# pj14.net
KiCad netlist of a schematic drawn in EAGLE
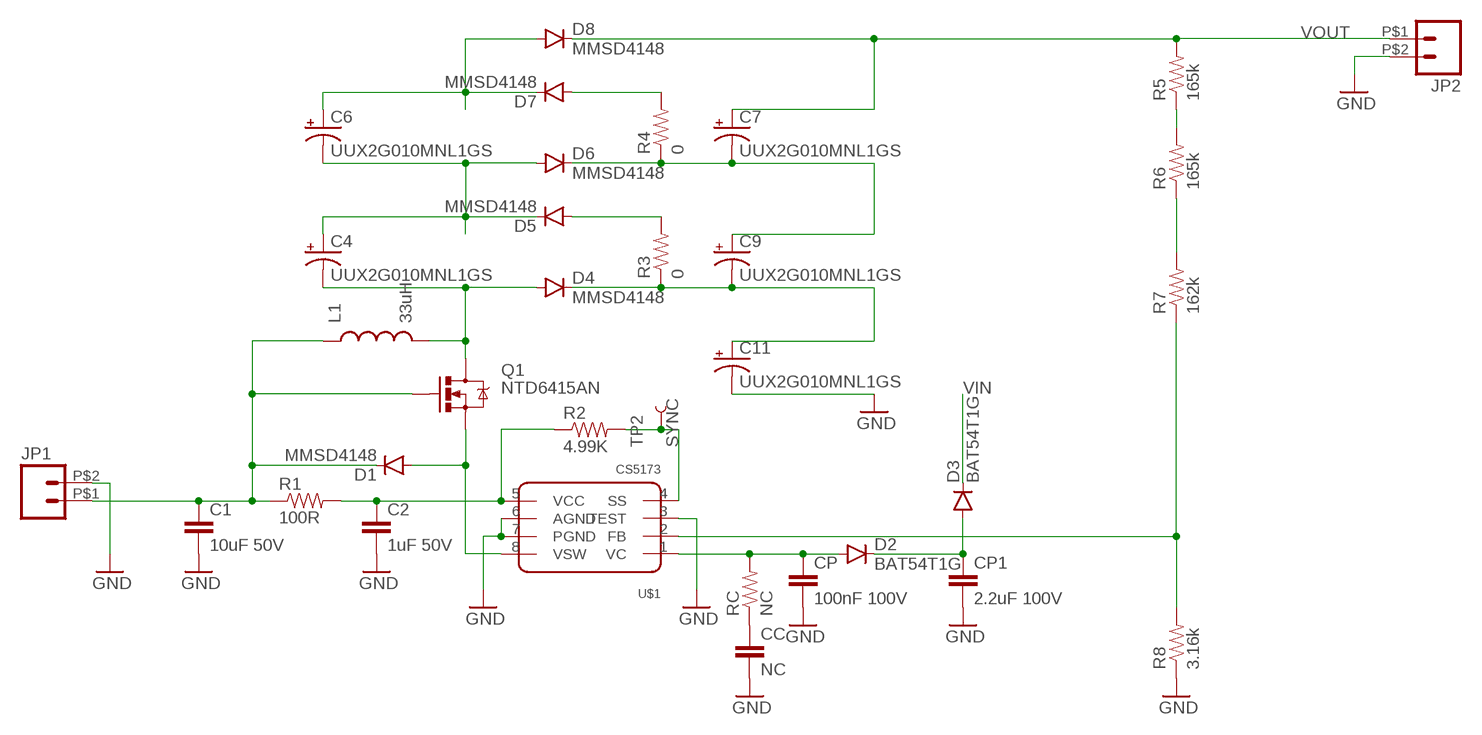
[diagram p0: schematic, sheet 1]

(export (version "E")
  (design (tool "Eeschema 10.0.6"))
  (components
    (comp (ref "C1")
      (value "10uF 50V")
      (footprint "eagle-import:1210")
      (libsource (lib "eagle-import") (part "10UF50V20%(1210)"))
    )
    (comp (ref "C2")
      (value "1uF 50V")
      (footprint "eagle-import:1210")
      (libsource (lib "eagle-import") (part "10UF50V20%(1210)"))
    )
    (comp (ref "C4")
      (value "UUX2G010MNL1GS")
      (footprint "eagle-import:PANASONIC_E")
      (libsource (lib "eagle-import") (part "CAP_POLE"))
    )
    (comp (ref "C6")
      (value "UUX2G010MNL1GS")
      (footprint "eagle-import:PANASONIC_E")
      (libsource (lib "eagle-import") (part "CAP_POLE"))
    )
    (comp (ref "C7")
      (value "UUX2G010MNL1GS")
      (footprint "eagle-import:PANASONIC_E")
      (libsource (lib "eagle-import") (part "CAP_POLE"))
    )
    (comp (ref "C9")
      (value "UUX2G010MNL1GS")
      (footprint "eagle-import:PANASONIC_E")
      (libsource (lib "eagle-import") (part "CAP_POLE"))
    )
    (comp (ref "C11")
      (value "UUX2G010MNL1GS")
      (footprint "eagle-import:PANASONIC_E")
      (libsource (lib "eagle-import") (part "CAP_POLE"))
    )
    (comp (ref "CC")
      (value "NC")
      (footprint "eagle-import:0603-CAP")
      (libsource (lib "eagle-import") (part "1.2PF-50V-20%(0603)"))
    )
    (comp (ref "CP")
      (value "100nF 100V")
      (footprint "eagle-import:0603-CAP")
      (libsource (lib "eagle-import") (part "1.2PF-50V-20%(0603)"))
    )
    (comp (ref "CP1")
      (value "2.2uF 100V")
      (footprint "eagle-import:1210")
      (libsource (lib "eagle-import") (part "10UF50V20%(1210)"))
    )
    (comp (ref "D1")
      (value "MMSD4148")
      (footprint "eagle-import:SOD-123")
      (libsource (lib "eagle-import") (part "DIODESOD123"))
    )
    (comp (ref "D2")
      (value "BAT54T1G")
      (footprint "eagle-import:SOD-123")
      (libsource (lib "eagle-import") (part "DIODESOD123"))
    )
    (comp (ref "D3")
      (value "BAT54T1G")
      (footprint "eagle-import:SOD-123")
      (libsource (lib "eagle-import") (part "DIODESOD123"))
    )
    (comp (ref "D4")
      (value "MMSD4148")
      (footprint "eagle-import:SOD-123")
      (libsource (lib "eagle-import") (part "DIODESOD123"))
    )
    (comp (ref "D5")
      (value "MMSD4148")
      (footprint "eagle-import:SOD-123")
      (libsource (lib "eagle-import") (part "DIODESOD123"))
    )
    (comp (ref "D6")
      (value "MMSD4148")
      (footprint "eagle-import:SOD-123")
      (libsource (lib "eagle-import") (part "DIODESOD123"))
    )
    (comp (ref "D7")
      (value "MMSD4148")
      (footprint "eagle-import:SOD-123")
      (libsource (lib "eagle-import") (part "DIODESOD123"))
    )
    (comp (ref "D8")
      (value "MMSD4148")
      (footprint "eagle-import:SOD-123")
      (libsource (lib "eagle-import") (part "DIODESOD123"))
    )
    (comp (ref "JP1")
      (value "M02")
      (footprint "eagle-import:1X02_5.08")
      (libsource (lib "eagle-import") (part "M02"))
    )
    (comp (ref "JP2")
      (value "M02")
      (footprint "eagle-import:1X02_5.08")
      (libsource (lib "eagle-import") (part "M02"))
    )
    (comp (ref "L1")
      (value "33uH")
      (footprint "eagle-import:CDRH125")
      (libsource (lib "eagle-import") (part "INDUCTORPWR"))
    )
    (comp (ref "Q1")
      (value "NTD6415AN")
      (footprint "eagle-import:DPAK")
      (libsource (lib "eagle-import") (part "MOSFET-NCHANNELFDD8780"))
    )
    (comp (ref "R1")
      (value "100R")
      (footprint "eagle-import:0603-RES")
      (libsource (lib "eagle-import") (part "2.0KOHM1/10W5%(0603)"))
    )
    (comp (ref "R2")
      (value "4.99K")
      (footprint "eagle-import:0603-RES")
      (libsource (lib "eagle-import") (part "2.0KOHM1/10W5%(0603)"))
    )
    (comp (ref "R3")
      (value "0")
      (footprint "eagle-import:0603-RES")
      (libsource (lib "eagle-import") (part "2.0KOHM1/10W5%(0603)"))
    )
    (comp (ref "R4")
      (value "0")
      (footprint "eagle-import:0603-RES")
      (libsource (lib "eagle-import") (part "2.0KOHM1/10W5%(0603)"))
    )
    (comp (ref "R5")
      (value "165k")
      (footprint "eagle-import:0603-RES")
      (libsource (lib "eagle-import") (part "2.0KOHM1/10W5%(0603)"))
    )
    (comp (ref "R6")
      (value "165k")
      (footprint "eagle-import:0603-RES")
      (libsource (lib "eagle-import") (part "2.0KOHM1/10W5%(0603)"))
    )
    (comp (ref "R7")
      (value "162k")
      (footprint "eagle-import:0603-RES")
      (libsource (lib "eagle-import") (part "2.0KOHM1/10W5%(0603)"))
    )
    (comp (ref "R8")
      (value "3.16k")
      (footprint "eagle-import:0603-RES")
      (libsource (lib "eagle-import") (part "2.0KOHM1/10W5%(0603)"))
    )
    (comp (ref "RC")
      (value "NC")
      (footprint "eagle-import:0603-RES")
      (libsource (lib "eagle-import") (part "2.0KOHM1/10W5%(0603)"))
    )
    (comp (ref "TP2")
      (value "SYNC")
      (footprint "eagle-import:PAD.03X.03")
      (libsource (lib "eagle-import") (part "TEST-POINT3"))
    )
    (comp (ref "U$1")
      (value "CS5173")
      (footprint "eagle-import:SOIC−8")
      (libsource (lib "eagle-import") (part "CS5173"))
    )
  )
  (nets
    (net (code "1") (name "/VIN") (class "Default")
      (node (ref "C1") (pin "1") (pinfunction "1_1") (pintype "passive"))
      (node (ref "D1") (pin "C") (pinfunction "C_C") (pintype "passive"))
      (node (ref "D3") (pin "C") (pinfunction "C_C") (pintype "passive"))
      (node (ref "JP1") (pin "P$1") (pinfunction "1_P$1") (pintype "passive"))
      (node (ref "L1") (pin "1") (pinfunction "1_1") (pintype "passive"))
      (node (ref "Q1") (pin "1") (pinfunction "G_1") (pintype "passive"))
      (node (ref "R1") (pin "1") (pinfunction "1_1") (pintype "passive"))
    )
    (net (code "2") (name "/VOUT") (class "Default")
      (node (ref "C7") (pin "+") (pinfunction "+_+") (pintype "passive"))
      (node (ref "D8") (pin "C") (pinfunction "C_C") (pintype "passive"))
      (node (ref "JP2") (pin "P$1") (pinfunction "1_P$1") (pintype "passive"))
      (node (ref "R5") (pin "2") (pinfunction "2_2") (pintype "passive"))
    )
    (net (code "3") (name "GND") (class "Default")
      (node (ref "C1") (pin "2") (pinfunction "2_2") (pintype "passive"))
      (node (ref "C11") (pin "-") (pinfunction "-_-") (pintype "passive"))
      (node (ref "C2") (pin "2") (pinfunction "2_2") (pintype "passive"))
      (node (ref "CC") (pin "2") (pinfunction "2_2") (pintype "passive"))
      (node (ref "CP") (pin "2") (pinfunction "2_2") (pintype "passive"))
      (node (ref "CP1") (pin "2") (pinfunction "2_2") (pintype "passive"))
      (node (ref "JP1") (pin "P$2") (pinfunction "2_P$2") (pintype "passive"))
      (node (ref "JP2") (pin "P$2") (pinfunction "2_P$2") (pintype "passive"))
      (node (ref "R8") (pin "1") (pinfunction "1_1") (pintype "passive"))
      (node (ref "U$1") (pin "3") (pinfunction "TEST_3") (pintype "bidirectional"))
      (node (ref "U$1") (pin "6") (pinfunction "AGND_6") (pintype "bidirectional"))
      (node (ref "U$1") (pin "7") (pinfunction "PGND_7") (pintype "bidirectional"))
    )
    (net (code "4") (name "Net-(C4-Pad+)") (class "Default")
      (node (ref "C4") (pin "+") (pinfunction "+_+") (pintype "passive"))
      (node (ref "C6") (pin "-") (pinfunction "-_-") (pintype "passive"))
      (node (ref "D5") (pin "C") (pinfunction "C_C") (pintype "passive"))
      (node (ref "D6") (pin "A") (pinfunction "A_A") (pintype "passive"))
    )
    (net (code "5") (name "Net-(C6-Pad+)") (class "Default")
      (node (ref "C6") (pin "+") (pinfunction "+_+") (pintype "passive"))
      (node (ref "D7") (pin "C") (pinfunction "C_C") (pintype "passive"))
      (node (ref "D8") (pin "A") (pinfunction "A_A") (pintype "passive"))
    )
    (net (code "6") (name "Net-(C7-Pad-)") (class "Default")
      (node (ref "C7") (pin "-") (pinfunction "-_-") (pintype "passive"))
      (node (ref "C9") (pin "+") (pinfunction "+_+") (pintype "passive"))
      (node (ref "D6") (pin "C") (pinfunction "C_C") (pintype "passive"))
      (node (ref "R4") (pin "1") (pinfunction "1_1") (pintype "passive"))
    )
    (net (code "7") (name "Net-(C11-Pad+)") (class "Default")
      (node (ref "C11") (pin "+") (pinfunction "+_+") (pintype "passive"))
      (node (ref "C9") (pin "-") (pinfunction "-_-") (pintype "passive"))
      (node (ref "D4") (pin "C") (pinfunction "C_C") (pintype "passive"))
      (node (ref "R3") (pin "1") (pinfunction "1_1") (pintype "passive"))
    )
    (net (code "8") (name "Net-(CC-Pad1)") (class "Default")
      (node (ref "CC") (pin "1") (pinfunction "1_1") (pintype "passive"))
      (node (ref "RC") (pin "1") (pinfunction "1_1") (pintype "passive"))
    )
    (net (code "9") (name "Net-(CP1-Pad1)") (class "Default")
      (node (ref "CP1") (pin "1") (pinfunction "1_1") (pintype "passive"))
      (node (ref "D2") (pin "C") (pinfunction "C_C") (pintype "passive"))
      (node (ref "D3") (pin "A") (pinfunction "A_A") (pintype "passive"))
    )
    (net (code "10") (name "Net-(D5-PadA)") (class "Default")
      (node (ref "D5") (pin "A") (pinfunction "A_A") (pintype "passive"))
      (node (ref "R3") (pin "2") (pinfunction "2_2") (pintype "passive"))
    )
    (net (code "11") (name "Net-(D7-PadA)") (class "Default")
      (node (ref "D7") (pin "A") (pinfunction "A_A") (pintype "passive"))
      (node (ref "R4") (pin "2") (pinfunction "2_2") (pintype "passive"))
    )
    (net (code "12") (name "Net-(Q1-D)") (class "Default")
      (node (ref "C4") (pin "-") (pinfunction "-_-") (pintype "passive"))
      (node (ref "D4") (pin "A") (pinfunction "A_A") (pintype "passive"))
      (node (ref "L1") (pin "2") (pinfunction "2_2") (pintype "passive"))
      (node (ref "Q1") (pin "4") (pinfunction "D_4") (pintype "passive"))
    )
    (net (code "13") (name "Net-(Q1-S)") (class "Default")
      (node (ref "D1") (pin "A") (pinfunction "A_A") (pintype "passive"))
      (node (ref "Q1") (pin "3") (pinfunction "S_3") (pintype "passive"))
      (node (ref "U$1") (pin "8") (pinfunction "VSW_8") (pintype "bidirectional"))
    )
    (net (code "14") (name "Net-(R5-Pad1)") (class "Default")
      (node (ref "R5") (pin "1") (pinfunction "1_1") (pintype "passive"))
      (node (ref "R6") (pin "2") (pinfunction "2_2") (pintype "passive"))
    )
    (net (code "15") (name "Net-(R6-Pad1)") (class "Default")
      (node (ref "R6") (pin "1") (pinfunction "1_1") (pintype "passive"))
      (node (ref "R7") (pin "2") (pinfunction "2_2") (pintype "passive"))
    )
    (net (code "16") (name "Net-(TP2-1)") (class "Default")
      (node (ref "R2") (pin "2") (pinfunction "2_2") (pintype "passive"))
      (node (ref "TP2") (pin "P$1") (pinfunction "1_P$1") (pintype "bidirectional"))
      (node (ref "U$1") (pin "4") (pinfunction "SS_4") (pintype "bidirectional"))
    )
    (net (code "17") (name "Net-(U$1-FB)") (class "Default")
      (node (ref "R7") (pin "1") (pinfunction "1_1") (pintype "passive"))
      (node (ref "R8") (pin "2") (pinfunction "2_2") (pintype "passive"))
      (node (ref "U$1") (pin "2") (pinfunction "FB_2") (pintype "bidirectional"))
    )
    (net (code "18") (name "Net-(U$1-VC)") (class "Default")
      (node (ref "CP") (pin "1") (pinfunction "1_1") (pintype "passive"))
      (node (ref "D2") (pin "A") (pinfunction "A_A") (pintype "passive"))
      (node (ref "RC") (pin "2") (pinfunction "2_2") (pintype "passive"))
      (node (ref "U$1") (pin "1") (pinfunction "VC_1") (pintype "bidirectional"))
    )
    (net (code "19") (name "Net-(U$1-VCC)") (class "Default")
      (node (ref "C2") (pin "1") (pinfunction "1_1") (pintype "passive"))
      (node (ref "R1") (pin "2") (pinfunction "2_2") (pintype "passive"))
      (node (ref "R2") (pin "1") (pinfunction "1_1") (pintype "passive"))
      (node (ref "U$1") (pin "5") (pinfunction "VCC_5") (pintype "bidirectional"))
    )
  )
)
